# Connectors.net
KiCad netlist of a schematic drawn in Altium Designer
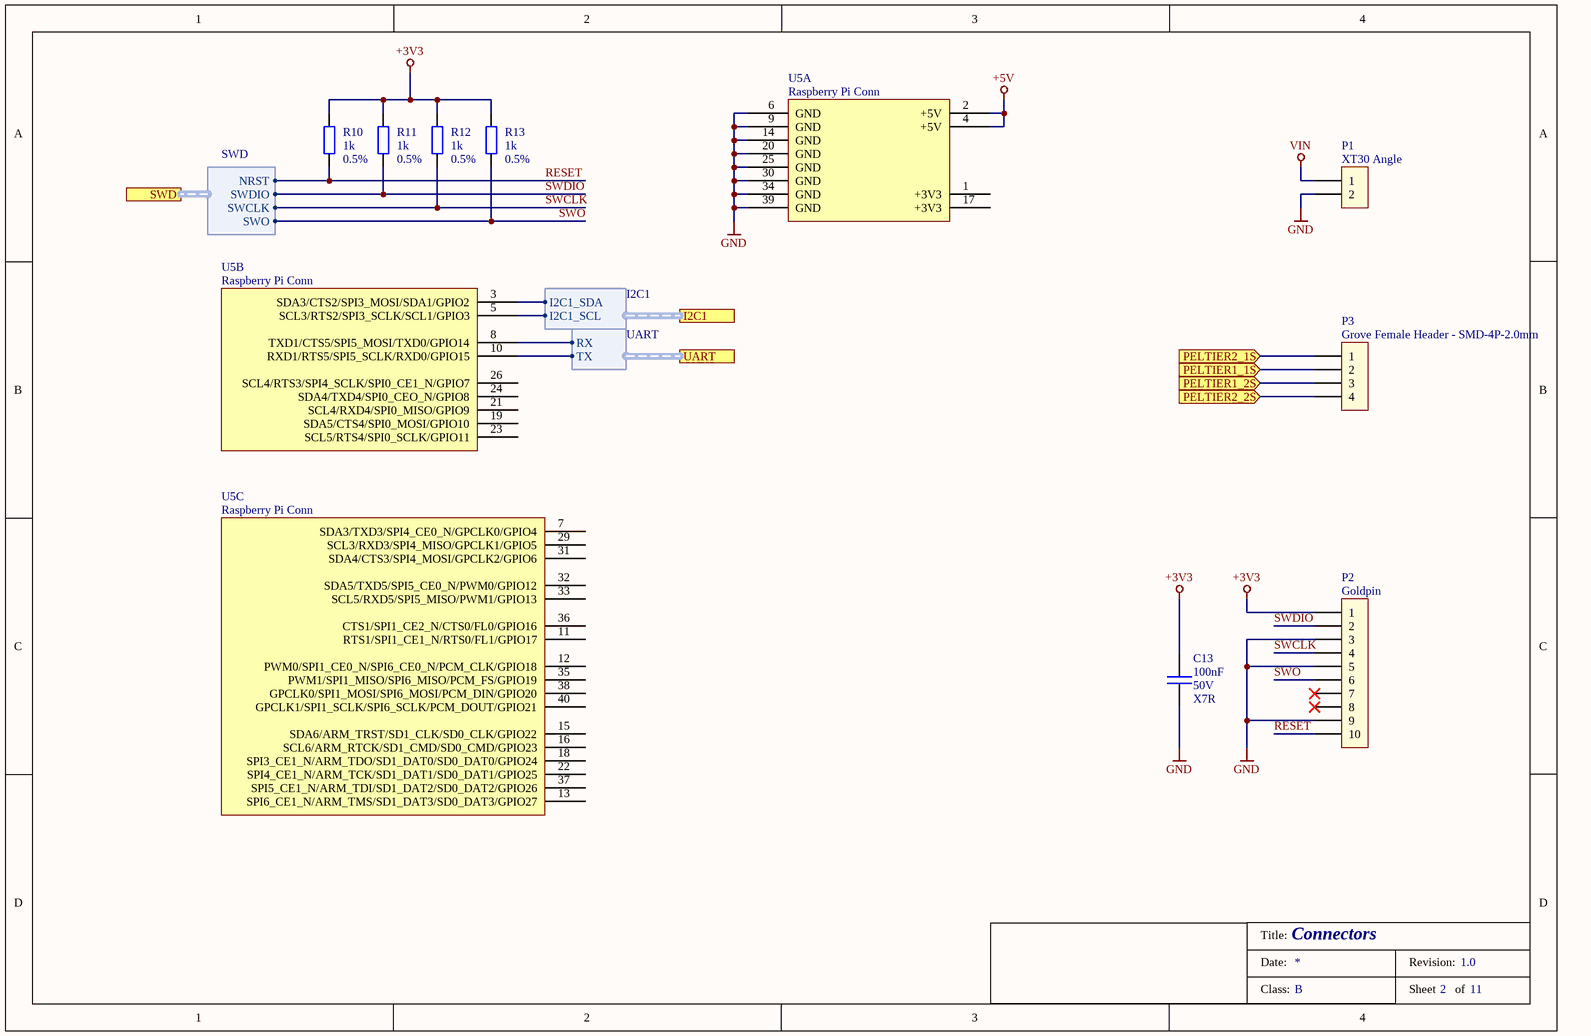
[diagram p0: Connectors.SchDoc]

(export (version "E")
  (design (tool "Eeschema 10.0.6"))
  (components
    (comp (ref "C13")
      (value "100nF")
      (footprint "C_0603")
      (description "Capacitor")
      (fields
        (field (name "VOLTAGE") "50V")
        (field (name "DIELECTRIC") "X7R")
        (field (name "PART NUMBER") "C_100nF_50V_0603")
        (field (name "MANUFACTURER") "Kemet")
      )
      (libsource (lib "ProgresjaSpace") (part "C"))
    )
    (comp (ref "P1")
      (value "P_Header_2")
      (footprint "XT30_ANGL")
      (description "XT30 Angle")
      (fields
        (field (name "DESC") "XT30 Angle")
        (field (name "PART NUMBER") "XT30-ANGLE")
        (field (name "MANUFACTURER") "DFRobot")
      )
      (libsource (lib "ProgresjaSpace") (part "P_Header_2"))
    )
    (comp (ref "P2")
      (value "P_Header_10")
      (footprint "CONN_M50_3610542")
      (description "Goldpin")
      (fields
        (field (name "DESC") "Goldpin")
        (field (name "PART NUMBER") "M50-3610542")
        (field (name "MANUFACTURER") "Harwin")
      )
      (libsource (lib "ProgresjaSpace") (part "P_Header_10"))
    )
    (comp (ref "P3")
      (value "P_Header_4")
      (footprint "CONN_114020164")
      (description "Grove Female Header - SMD-4P-2.0mm")
      (fields
        (field (name "DESC") "Grove Female Header - SMD-4P-2.0mm")
        (field (name "PART NUMBER") "114020164")
        (field (name "MANUFACTURER") "SEEED")
      )
      (libsource (lib "ProgresjaSpace") (part "P_Header_4"))
    )
    (comp (ref "R10")
      (value "1k")
      (footprint "R_0402")
      (fields
        (field (name "TOLERANCE") "0.5%")
        (field (name "PART NUMBER") "R_1k_50V_0402")
        (field (name "VOLTAGE") "50V")
        (field (name "MANUFACTURER") "Vishay")
      )
      (libsource (lib "ProgresjaSpace") (part "R"))
    )
    (comp (ref "R11")
      (value "1k")
      (footprint "R_0402")
      (fields
        (field (name "TOLERANCE") "0.5%")
        (field (name "PART NUMBER") "R_1k_50V_0402")
        (field (name "VOLTAGE") "50V")
        (field (name "MANUFACTURER") "Vishay")
      )
      (libsource (lib "ProgresjaSpace") (part "R"))
    )
    (comp (ref "R12")
      (value "1k")
      (footprint "R_0402")
      (fields
        (field (name "TOLERANCE") "0.5%")
        (field (name "PART NUMBER") "R_1k_50V_0402")
        (field (name "VOLTAGE") "50V")
        (field (name "MANUFACTURER") "Vishay")
      )
      (libsource (lib "ProgresjaSpace") (part "R"))
    )
    (comp (ref "R13")
      (value "1k")
      (footprint "R_0402")
      (fields
        (field (name "TOLERANCE") "0.5%")
        (field (name "PART NUMBER") "R_1k_50V_0402")
        (field (name "VOLTAGE") "50V")
        (field (name "MANUFACTURER") "Vishay")
      )
      (libsource (lib "ProgresjaSpace") (part "R"))
    )
    (comp (ref "U5")
      (value "Raspberry Pi Conn")
      (footprint "CONN_Raspberry_Pi")
      (description "Raspberry Pi female connector")
      (fields
        (field (name "PART NUMBER") "CONN_Raspberry_Pi")
        (field (name "MANUFACTURER") "TE Connectivity")
      )
      (libsource (lib "ProgresjaSpace") (part "M_Raspberry_Pi_4B"))
    )
  )
  (nets
    (net (code "4") (name "+3V3") (class "Default")
      (node (ref "C13") (pin "1") (pinfunction "1_1") (pintype "passive"))
      (node (ref "P2") (pin "1") (pinfunction "1_1") (pintype "passive"))
      (node (ref "R10") (pin "1") (pinfunction "1_1") (pintype "passive"))
      (node (ref "R11") (pin "1") (pinfunction "1_1") (pintype "passive"))
      (node (ref "R12") (pin "1") (pinfunction "1_1") (pintype "passive"))
      (node (ref "R13") (pin "1") (pinfunction "1_1") (pintype "passive"))
    )
    (net (code "5") (name "+5V") (class "Default")
      (node (ref "U5") (pin "2") (pinfunction "+5V_2") (pintype "passive"))
      (node (ref "U5") (pin "4") (pinfunction "+5V_4") (pintype "passive"))
    )
    (net (code "6") (name "/I2C1_SCL") (class "Default")
      (node (ref "U5") (pin "5") (pinfunction "SCL3/RTS2/SPI3_SCLK/SCL1/GPIO3_5") (pintype "passive"))
    )
    (net (code "7") (name "/I2C1_SDA") (class "Default")
      (node (ref "U5") (pin "3") (pinfunction "SDA3/CTS2/SPI3_MOSI/SDA1/GPIO2_3") (pintype "passive"))
    )
    (net (code "8") (name "/PELTIER1_1S") (class "Default")
      (node (ref "P3") (pin "2") (pinfunction "2_2") (pintype "passive"))
    )
    (net (code "9") (name "/PELTIER1_2S") (class "Default")
      (node (ref "P3") (pin "3") (pinfunction "3_3") (pintype "passive"))
    )
    (net (code "10") (name "/PELTIER2_1S") (class "Default")
      (node (ref "P3") (pin "1") (pinfunction "1_1") (pintype "passive"))
    )
    (net (code "11") (name "/PELTIER2_2S") (class "Default")
      (node (ref "P3") (pin "4") (pinfunction "4_4") (pintype "passive"))
    )
    (net (code "12") (name "/RESET") (class "Default")
      (node (ref "P2") (pin "10") (pinfunction "10_10") (pintype "passive"))
      (node (ref "R10") (pin "2") (pinfunction "2_2") (pintype "passive"))
    )
    (net (code "13") (name "/RX") (class "Default")
      (node (ref "U5") (pin "8") (pinfunction "TXD1/CTS5/SPI5_MOSI/TXD0/GPIO14_8") (pintype "passive"))
    )
    (net (code "14") (name "/SWCLK") (class "Default")
      (node (ref "P2") (pin "4") (pinfunction "4_4") (pintype "passive"))
      (node (ref "R12") (pin "2") (pinfunction "2_2") (pintype "passive"))
    )
    (net (code "15") (name "/SWDIO") (class "Default")
      (node (ref "P2") (pin "2") (pinfunction "2_2") (pintype "passive"))
      (node (ref "R11") (pin "2") (pinfunction "2_2") (pintype "passive"))
    )
    (net (code "16") (name "/SWO") (class "Default")
      (node (ref "P2") (pin "6") (pinfunction "6_6") (pintype "passive"))
      (node (ref "R13") (pin "2") (pinfunction "2_2") (pintype "passive"))
    )
    (net (code "17") (name "/TX") (class "Default")
      (node (ref "U5") (pin "10") (pinfunction "RXD1/RTS5/SPI5_SCLK/RXD0/GPIO15_10") (pintype "passive"))
    )
    (net (code "21") (name "GND") (class "Default")
      (node (ref "C13") (pin "2") (pinfunction "2_2") (pintype "passive"))
      (node (ref "P1") (pin "2") (pinfunction "2_2") (pintype "passive"))
      (node (ref "P2") (pin "3") (pinfunction "3_3") (pintype "passive"))
      (node (ref "P2") (pin "5") (pinfunction "5_5") (pintype "passive"))
      (node (ref "P2") (pin "9") (pinfunction "9_9") (pintype "passive"))
      (node (ref "U5") (pin "14") (pinfunction "GND_14") (pintype "passive"))
      (node (ref "U5") (pin "20") (pinfunction "GND_20") (pintype "passive"))
      (node (ref "U5") (pin "25") (pinfunction "GND_25") (pintype "passive"))
      (node (ref "U5") (pin "30") (pinfunction "GND_30") (pintype "passive"))
      (node (ref "U5") (pin "34") (pinfunction "GND_34") (pintype "passive"))
      (node (ref "U5") (pin "39") (pinfunction "GND_39") (pintype "passive"))
      (node (ref "U5") (pin "6") (pinfunction "GND_6") (pintype "passive"))
      (node (ref "U5") (pin "9") (pinfunction "GND_9") (pintype "passive"))
    )
    (net (code "22") (name "VIN") (class "Default")
      (node (ref "P1") (pin "1") (pinfunction "1_1") (pintype "passive"))
    )
    (net (code "23") (name "unconnected-(P2-Pad7)") (class "Default")
      (node (ref "P2") (pin "7") (pinfunction "7_7") (pintype "passive+no_connect"))
    )
    (net (code "24") (name "unconnected-(P2-Pad8)") (class "Default")
      (node (ref "P2") (pin "8") (pinfunction "8_8") (pintype "passive+no_connect"))
    )
    (net (code "25") (name "unconnected-(U5A-+3V3-Pad1)") (class "Default")
      (node (ref "U5") (pin "1") (pinfunction "+3V3_1") (pintype "passive"))
    )
    (net (code "26") (name "unconnected-(U5A-+3V3-Pad17)") (class "Default")
      (node (ref "U5") (pin "17") (pinfunction "+3V3_17") (pintype "passive"))
    )
    (net (code "27") (name "unconnected-(U5B-SCL4{slash}RTS3{slash}SPI4_SCLK{slash}SPI0_CE1_N{slash}GPIO7-Pad26)") (class "Default")
      (node (ref "U5") (pin "26") (pinfunction "SCL4/RTS3/SPI4_SCLK/SPI0_CE1_N/GPIO7_26") (pintype "passive"))
    )
    (net (code "28") (name "unconnected-(U5B-SCL4{slash}RXD4{slash}SPI0_MISO{slash}GPIO9-Pad21)") (class "Default")
      (node (ref "U5") (pin "21") (pinfunction "SCL4/RXD4/SPI0_MISO/GPIO9_21") (pintype "passive"))
    )
    (net (code "29") (name "unconnected-(U5B-SCL5{slash}RTS4{slash}SPI0_SCLK{slash}GPIO11-Pad23)") (class "Default")
      (node (ref "U5") (pin "23") (pinfunction "SCL5/RTS4/SPI0_SCLK/GPIO11_23") (pintype "passive"))
    )
    (net (code "30") (name "unconnected-(U5B-SDA4{slash}TXD4{slash}SPI0_CEO_N{slash}GPIO8-Pad24)") (class "Default")
      (node (ref "U5") (pin "24") (pinfunction "SDA4/TXD4/SPI0_CEO_N/GPIO8_24") (pintype "passive"))
    )
    (net (code "31") (name "unconnected-(U5B-SDA5{slash}CTS4{slash}SPI0_MOSI{slash}GPIO10-Pad19)") (class "Default")
      (node (ref "U5") (pin "19") (pinfunction "SDA5/CTS4/SPI0_MOSI/GPIO10_19") (pintype "passive"))
    )
    (net (code "32") (name "unconnected-(U5C-CTS1{slash}SPI1_CE2_N{slash}CTS0{slash}FL0{slash}GPIO16-Pad36)") (class "Default")
      (node (ref "U5") (pin "36") (pinfunction "CTS1/SPI1_CE2_N/CTS0/FL0/GPIO16_36") (pintype "passive"))
    )
    (net (code "33") (name "unconnected-(U5C-GPCLK0{slash}SPI1_MOSI{slash}SPI6_MOSI{slash}PCM_DIN{slash}GPIO20-Pad38)") (class "Default")
      (node (ref "U5") (pin "38") (pinfunction "GPCLK0/SPI1_MOSI/SPI6_MOSI/PCM_DIN/GPIO20_38") (pintype "passive"))
    )
    (net (code "34") (name "unconnected-(U5C-GPCLK1{slash}SPI1_SCLK{slash}SPI6_SCLK{slash}PCM_DOUT{slash}GPIO21-Pad40)") (class "Default")
      (node (ref "U5") (pin "40") (pinfunction "GPCLK1/SPI1_SCLK/SPI6_SCLK/PCM_DOUT/GPIO21_40") (pintype "passive"))
    )
    (net (code "35") (name "unconnected-(U5C-PWM0{slash}SPI1_CE0_N{slash}SPI6_CE0_N{slash}PCM_CLK{slash}GPIO18-Pad12)") (class "Default")
      (node (ref "U5") (pin "12") (pinfunction "PWM0/SPI1_CE0_N/SPI6_CE0_N/PCM_CLK/GPIO18_12") (pintype "passive"))
    )
    (net (code "36") (name "unconnected-(U5C-PWM1{slash}SPI1_MISO{slash}SPI6_MISO{slash}PCM_FS{slash}GPIO19-Pad35)") (class "Default")
      (node (ref "U5") (pin "35") (pinfunction "PWM1/SPI1_MISO/SPI6_MISO/PCM_FS/GPIO19_35") (pintype "passive"))
    )
    (net (code "37") (name "unconnected-(U5C-RTS1{slash}SPI1_CE1_N{slash}RTS0{slash}FL1{slash}GPIO17-Pad11)") (class "Default")
      (node (ref "U5") (pin "11") (pinfunction "RTS1/SPI1_CE1_N/RTS0/FL1/GPIO17_11") (pintype "passive"))
    )
    (net (code "38") (name "unconnected-(U5C-SCL3{slash}RXD3{slash}SPI4_MISO{slash}GPCLK1{slash}GPIO5-Pad29)") (class "Default")
      (node (ref "U5") (pin "29") (pinfunction "SCL3/RXD3/SPI4_MISO/GPCLK1/GPIO5_29") (pintype "passive"))
    )
    (net (code "39") (name "unconnected-(U5C-SCL5{slash}RXD5{slash}SPI5_MISO{slash}PWM1{slash}GPIO13-Pad33)") (class "Default")
      (node (ref "U5") (pin "33") (pinfunction "SCL5/RXD5/SPI5_MISO/PWM1/GPIO13_33") (pintype "passive"))
    )
    (net (code "40") (name "unconnected-(U5C-SCL6{slash}ARM_RTCK{slash}SD1_CMD{slash}SD0_CMD{slash}GPIO23-Pad16)") (class "Default")
      (node (ref "U5") (pin "16") (pinfunction "SCL6/ARM_RTCK/SD1_CMD/SD0_CMD/GPIO23_16") (pintype "passive"))
    )
    (net (code "41") (name "unconnected-(U5C-SDA3{slash}TXD3{slash}SPI4_CE0_N{slash}GPCLK0{slash}GPIO4-Pad7)") (class "Default")
      (node (ref "U5") (pin "7") (pinfunction "SDA3/TXD3/SPI4_CE0_N/GPCLK0/GPIO4_7") (pintype "passive"))
    )
    (net (code "42") (name "unconnected-(U5C-SDA4{slash}CTS3{slash}SPI4_MOSI{slash}GPCLK2{slash}GPIO6-Pad31)") (class "Default")
      (node (ref "U5") (pin "31") (pinfunction "SDA4/CTS3/SPI4_MOSI/GPCLK2/GPIO6_31") (pintype "passive"))
    )
    (net (code "43") (name "unconnected-(U5C-SDA5{slash}TXD5{slash}SPI5_CE0_N{slash}PWM0{slash}GPIO12-Pad32)") (class "Default")
      (node (ref "U5") (pin "32") (pinfunction "SDA5/TXD5/SPI5_CE0_N/PWM0/GPIO12_32") (pintype "passive"))
    )
    (net (code "44") (name "unconnected-(U5C-SDA6{slash}ARM_TRST{slash}SD1_CLK{slash}SD0_CLK{slash}GPIO22-Pad15)") (class "Default")
      (node (ref "U5") (pin "15") (pinfunction "SDA6/ARM_TRST/SD1_CLK/SD0_CLK/GPIO22_15") (pintype "passive"))
    )
    (net (code "45") (name "unconnected-(U5C-SPI3_CE1_N{slash}ARM_TDO{slash}SD1_DAT0{slash}SD0_DAT0{slash}GPIO24-Pad18)") (class "Default")
      (node (ref "U5") (pin "18") (pinfunction "SPI3_CE1_N/ARM_TDO/SD1_DAT0/SD0_DAT0/GPIO24_18") (pintype "passive"))
    )
    (net (code "46") (name "unconnected-(U5C-SPI4_CE1_N{slash}ARM_TCK{slash}SD1_DAT1{slash}SD0_DAT1{slash}GPIO25-Pad22)") (class "Default")
      (node (ref "U5") (pin "22") (pinfunction "SPI4_CE1_N/ARM_TCK/SD1_DAT1/SD0_DAT1/GPIO25_22") (pintype "passive"))
    )
    (net (code "47") (name "unconnected-(U5C-SPI5_CE1_N{slash}ARM_TDI{slash}SD1_DAT2{slash}SD0_DAT2{slash}GPIO26-Pad37)") (class "Default")
      (node (ref "U5") (pin "37") (pinfunction "SPI5_CE1_N/ARM_TDI/SD1_DAT2/SD0_DAT2/GPIO26_37") (pintype "passive"))
    )
    (net (code "48") (name "unconnected-(U5C-SPI6_CE1_N{slash}ARM_TMS{slash}SD1_DAT3{slash}SD0_DAT3{slash}GPIO27-Pad13)") (class "Default")
      (node (ref "U5") (pin "13") (pinfunction "SPI6_CE1_N/ARM_TMS/SD1_DAT3/SD0_DAT3/GPIO27_13") (pintype "passive"))
    )
  )
)
